# TSMP-GLV.net
KiCad netlist of a schematic drawn in EAGLE
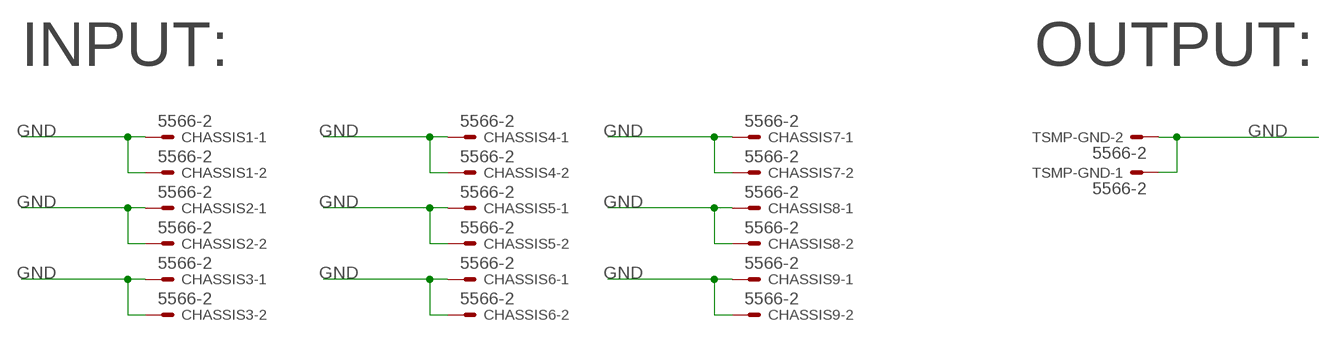
[diagram p0: schematic, sheet 1]

(export (version "E")
  (design (tool "Eeschema 10.0.6"))
  (components
    (comp (ref "CHASSIS1")
      (value "5566-2")
      (footprint "eagle-import:5566-2")
      (fields (field (name "MF") "MOLEX"))
      (libsource (lib "eagle-import") (part "5566-2"))
    )
    (comp (ref "CHASSIS2")
      (value "5566-2")
      (footprint "eagle-import:5566-2")
      (fields (field (name "MF") "MOLEX"))
      (libsource (lib "eagle-import") (part "5566-2"))
    )
    (comp (ref "CHASSIS3")
      (value "5566-2")
      (footprint "eagle-import:5566-2")
      (fields (field (name "MF") "MOLEX"))
      (libsource (lib "eagle-import") (part "5566-2"))
    )
    (comp (ref "CHASSIS4")
      (value "5566-2")
      (footprint "eagle-import:5566-2")
      (fields (field (name "MF") "MOLEX"))
      (libsource (lib "eagle-import") (part "5566-2"))
    )
    (comp (ref "CHASSIS5")
      (value "5566-2")
      (footprint "eagle-import:5566-2")
      (fields (field (name "MF") "MOLEX"))
      (libsource (lib "eagle-import") (part "5566-2"))
    )
    (comp (ref "CHASSIS6")
      (value "5566-2")
      (footprint "eagle-import:5566-2")
      (fields (field (name "MF") "MOLEX"))
      (libsource (lib "eagle-import") (part "5566-2"))
    )
    (comp (ref "CHASSIS7")
      (value "5566-2")
      (footprint "eagle-import:5566-2")
      (fields (field (name "MF") "MOLEX"))
      (libsource (lib "eagle-import") (part "5566-2"))
    )
    (comp (ref "CHASSIS8")
      (value "5566-2")
      (footprint "eagle-import:5566-2")
      (fields (field (name "MF") "MOLEX"))
      (libsource (lib "eagle-import") (part "5566-2"))
    )
    (comp (ref "CHASSIS9")
      (value "5566-2")
      (footprint "eagle-import:5566-2")
      (fields (field (name "MF") "MOLEX"))
      (libsource (lib "eagle-import") (part "5566-2"))
    )
    (comp (ref "TSMP-GND")
      (value "5566-2")
      (footprint "eagle-import:5566-2")
      (fields (field (name "MF") "MOLEX"))
      (libsource (lib "eagle-import") (part "5566-2"))
    )
  )
  (nets
    (net (code "1") (name "/GND") (class "Default")
      (node (ref "CHASSIS1") (pin "1") (pinfunction "S_1") (pintype "passive"))
      (node (ref "CHASSIS1") (pin "2") (pinfunction "S_2") (pintype "passive"))
      (node (ref "CHASSIS2") (pin "1") (pinfunction "S_1") (pintype "passive"))
      (node (ref "CHASSIS2") (pin "2") (pinfunction "S_2") (pintype "passive"))
      (node (ref "CHASSIS3") (pin "1") (pinfunction "S_1") (pintype "passive"))
      (node (ref "CHASSIS3") (pin "2") (pinfunction "S_2") (pintype "passive"))
      (node (ref "CHASSIS4") (pin "1") (pinfunction "S_1") (pintype "passive"))
      (node (ref "CHASSIS4") (pin "2") (pinfunction "S_2") (pintype "passive"))
      (node (ref "CHASSIS5") (pin "1") (pinfunction "S_1") (pintype "passive"))
      (node (ref "CHASSIS5") (pin "2") (pinfunction "S_2") (pintype "passive"))
      (node (ref "CHASSIS6") (pin "1") (pinfunction "S_1") (pintype "passive"))
      (node (ref "CHASSIS6") (pin "2") (pinfunction "S_2") (pintype "passive"))
      (node (ref "CHASSIS7") (pin "1") (pinfunction "S_1") (pintype "passive"))
      (node (ref "CHASSIS7") (pin "2") (pinfunction "S_2") (pintype "passive"))
      (node (ref "CHASSIS8") (pin "1") (pinfunction "S_1") (pintype "passive"))
      (node (ref "CHASSIS8") (pin "2") (pinfunction "S_2") (pintype "passive"))
      (node (ref "CHASSIS9") (pin "1") (pinfunction "S_1") (pintype "passive"))
      (node (ref "CHASSIS9") (pin "2") (pinfunction "S_2") (pintype "passive"))
      (node (ref "TSMP-GND") (pin "1") (pinfunction "S_1") (pintype "passive"))
      (node (ref "TSMP-GND") (pin "2") (pinfunction "S_2") (pintype "passive"))
    )
  )
)
